# 4_LORA.net
KiCad netlist of a schematic drawn in Altium Designer
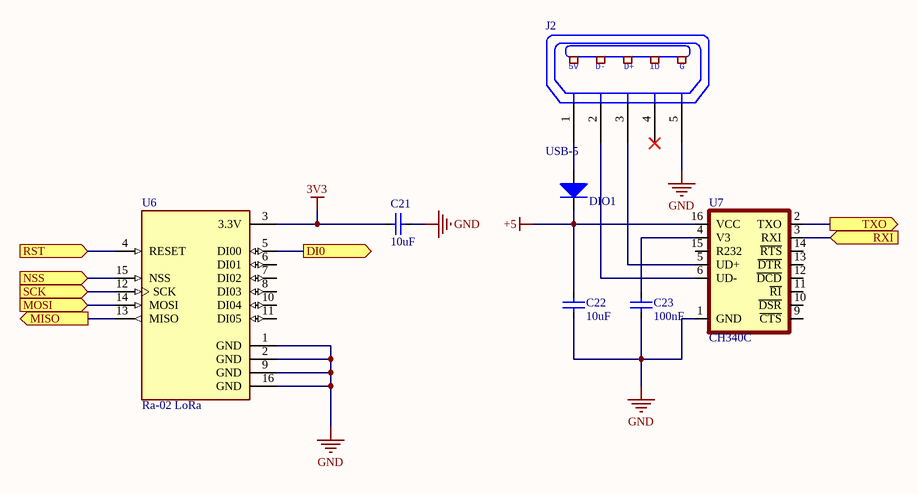
[diagram p0: [4]LORA.SchDoc]

(export (version "E")
  (design (tool "Eeschema 10.0.6"))
  (components
    (comp (ref "C21")
      (value "10uF")
      (footprint "CAP_0805")
      (description "Capacitor")
      (fields (field (name "PUBLISHER") "Altium Limited"))
      (libsource (lib "My Library") (part "CapSMD"))
    )
    (comp (ref "C22")
      (value "10uF")
      (footprint "CAP_0805")
      (description "Capacitor")
      (fields (field (name "PUBLISHER") "Altium Limited"))
      (libsource (lib "My Library") (part "CapSMD"))
    )
    (comp (ref "C23")
      (value "100nF")
      (footprint "CAP_0805")
      (description "Capacitor")
      (fields (field (name "PUBLISHER") "Altium Limited"))
      (libsource (lib "My Library") (part "CapSMD"))
    )
    (comp (ref "DIO1")
      (value "Diode SMD")
      (footprint "DIO-SMD-106")
      (description "Default Diode")
      (fields (field (name "PUBLISHER") "Altium Limited"))
      (libsource (lib "My Library") (part "Diode SMD"))
    )
    (comp (ref "J2")
      (value "USB-5")
      (footprint "USB-M1")
      (fields
        (field (name "MANUFACTURER") "FCI")
        (field (name "MANUFACTURER PART NUMBER") "10118193-0001LF")
        (field (name ".CREATOR") "MM")
        (field (name ".CHECKED PCB") "RF")
        (field (name ".CHECKED SCH") "MM")
      )
      (libsource (lib "My Library") (part "USB-5"))
    )
    (comp (ref "U6")
      (value "Ra-02 LoRa")
      (footprint "Ra-02")
      (description "LoRa Module Ra-02")
      (libsource (lib "My Library") (part "Ra-02 LoRa"))
    )
    (comp (ref "U7")
      (value "CH340C")
      (footprint "SOP-16")
      (description "USB to serial chip CH340")
      (fields (field (name "MF") "WCH"))
      (libsource (lib "My Library") (part "CH340C"))
    )
  )
  (nets
    (net (code "1") (name "+5") (class "Default")
      (node (ref "C22") (pin "2") (pinfunction "2_2") (pintype "passive"))
      (node (ref "DIO1") (pin "2") (pinfunction "K_2") (pintype "passive"))
      (node (ref "U7") (pin "16") (pinfunction "VCC_16") (pintype "bidirectional"))
    )
    (net (code "2") (name "/DI0") (class "Default")
      (node (ref "U6") (pin "5") (pinfunction "DI00_5") (pintype "bidirectional"))
    )
    (net (code "3") (name "/MISO") (class "Default")
      (node (ref "U6") (pin "13") (pinfunction "MISO_13") (pintype "output"))
    )
    (net (code "4") (name "/MOSI") (class "Default")
      (node (ref "U6") (pin "14") (pinfunction "MOSI_14") (pintype "input"))
    )
    (net (code "5") (name "/NSS") (class "Default")
      (node (ref "U6") (pin "15") (pinfunction "NSS_15") (pintype "input"))
    )
    (net (code "6") (name "/RST") (class "Default")
      (node (ref "U6") (pin "4") (pinfunction "RESET_4") (pintype "input"))
    )
    (net (code "7") (name "/RXI") (class "Default")
      (node (ref "U7") (pin "3") (pinfunction "RXI_3") (pintype "bidirectional"))
    )
    (net (code "8") (name "/SCK") (class "Default")
      (node (ref "U6") (pin "12") (pinfunction "SCK_12") (pintype "input"))
    )
    (net (code "9") (name "/TXO") (class "Default")
      (node (ref "U7") (pin "2") (pinfunction "TXO_2") (pintype "bidirectional"))
    )
    (net (code "10") (name "3V3") (class "Default")
      (node (ref "C21") (pin "1") (pinfunction "1_1") (pintype "passive"))
      (node (ref "U6") (pin "3") (pinfunction "3.3V_3") (pintype "power_in"))
    )
    (net (code "11") (name "GND") (class "Default")
      (node (ref "C21") (pin "2") (pinfunction "2_2") (pintype "passive"))
      (node (ref "C22") (pin "1") (pinfunction "1_1") (pintype "passive"))
      (node (ref "C23") (pin "1") (pinfunction "1_1") (pintype "passive"))
      (node (ref "J2") (pin "5") (pinfunction "P5_5") (pintype "passive"))
      (node (ref "U6") (pin "1") (pinfunction "GND_1") (pintype "power_in"))
      (node (ref "U6") (pin "16") (pinfunction "GND_16") (pintype "power_in"))
      (node (ref "U6") (pin "2") (pinfunction "GND_2") (pintype "power_in"))
      (node (ref "U6") (pin "9") (pinfunction "GND_9") (pintype "power_in"))
      (node (ref "U7") (pin "1") (pinfunction "GND_1") (pintype "bidirectional"))
    )
    (net (code "12") (name "Net-(DIO1-A)") (class "Default")
      (node (ref "DIO1") (pin "1") (pinfunction "A_1") (pintype "passive"))
      (node (ref "J2") (pin "1") (pinfunction "P1_1") (pintype "passive"))
    )
    (net (code "13") (name "Net-(J2-P2)") (class "Default")
      (node (ref "J2") (pin "2") (pinfunction "P2_2") (pintype "passive"))
      (node (ref "U7") (pin "6") (pinfunction "UD-_6") (pintype "bidirectional"))
    )
    (net (code "14") (name "Net-(J2-P3)") (class "Default")
      (node (ref "J2") (pin "3") (pinfunction "P3_3") (pintype "passive"))
      (node (ref "U7") (pin "5") (pinfunction "UD+_5") (pintype "bidirectional"))
    )
    (net (code "15") (name "Net-(U7-V3)") (class "Default")
      (node (ref "C23") (pin "2") (pinfunction "2_2") (pintype "passive"))
      (node (ref "U7") (pin "4") (pinfunction "V3_4") (pintype "bidirectional"))
    )
    (net (code "16") (name "unconnected-(J2-P4-Pad4)") (class "Default")
      (node (ref "J2") (pin "4") (pinfunction "P4_4") (pintype "passive+no_connect"))
    )
    (net (code "17") (name "unconnected-(U6-DI01-Pad6)") (class "Default")
      (node (ref "U6") (pin "6") (pinfunction "DI01_6") (pintype "bidirectional"))
    )
    (net (code "18") (name "unconnected-(U6-DI02-Pad7)") (class "Default")
      (node (ref "U6") (pin "7") (pinfunction "DI02_7") (pintype "bidirectional"))
    )
    (net (code "19") (name "unconnected-(U6-DI03-Pad8)") (class "Default")
      (node (ref "U6") (pin "8") (pinfunction "DI03_8") (pintype "bidirectional"))
    )
    (net (code "20") (name "unconnected-(U6-DI04-Pad10)") (class "Default")
      (node (ref "U6") (pin "10") (pinfunction "DI04_10") (pintype "bidirectional"))
    )
    (net (code "21") (name "unconnected-(U6-DI05-Pad11)") (class "Default")
      (node (ref "U6") (pin "11") (pinfunction "DI05_11") (pintype "bidirectional"))
    )
    (net (code "22") (name "unconnected-(U7-R232-Pad15)") (class "Default")
      (node (ref "U7") (pin "15") (pinfunction "R232_15") (pintype "bidirectional"))
    )
    (net (code "23") (name "unconnected-(U7-~{CTS}-Pad9)") (class "Default")
      (node (ref "U7") (pin "9") (pinfunction "~{CTS}_9") (pintype "bidirectional"))
    )
    (net (code "24") (name "unconnected-(U7-~{DCD}-Pad12)") (class "Default")
      (node (ref "U7") (pin "12") (pinfunction "~{DCD}_12") (pintype "bidirectional"))
    )
    (net (code "25") (name "unconnected-(U7-~{DSR}-Pad10)") (class "Default")
      (node (ref "U7") (pin "10") (pinfunction "~{DSR}_10") (pintype "bidirectional"))
    )
    (net (code "26") (name "unconnected-(U7-~{DTR}-Pad13)") (class "Default")
      (node (ref "U7") (pin "13") (pinfunction "~{DTR}_13") (pintype "bidirectional"))
    )
    (net (code "27") (name "unconnected-(U7-~{RI}-Pad11)") (class "Default")
      (node (ref "U7") (pin "11") (pinfunction "~{RI}_11") (pintype "bidirectional"))
    )
    (net (code "28") (name "unconnected-(U7-~{RTS}-Pad14)") (class "Default")
      (node (ref "U7") (pin "14") (pinfunction "~{RTS}_14") (pintype "bidirectional"))
    )
  )
)
